# wireless-therm-mk2.net
KiCad netlist of a schematic drawn in EAGLE
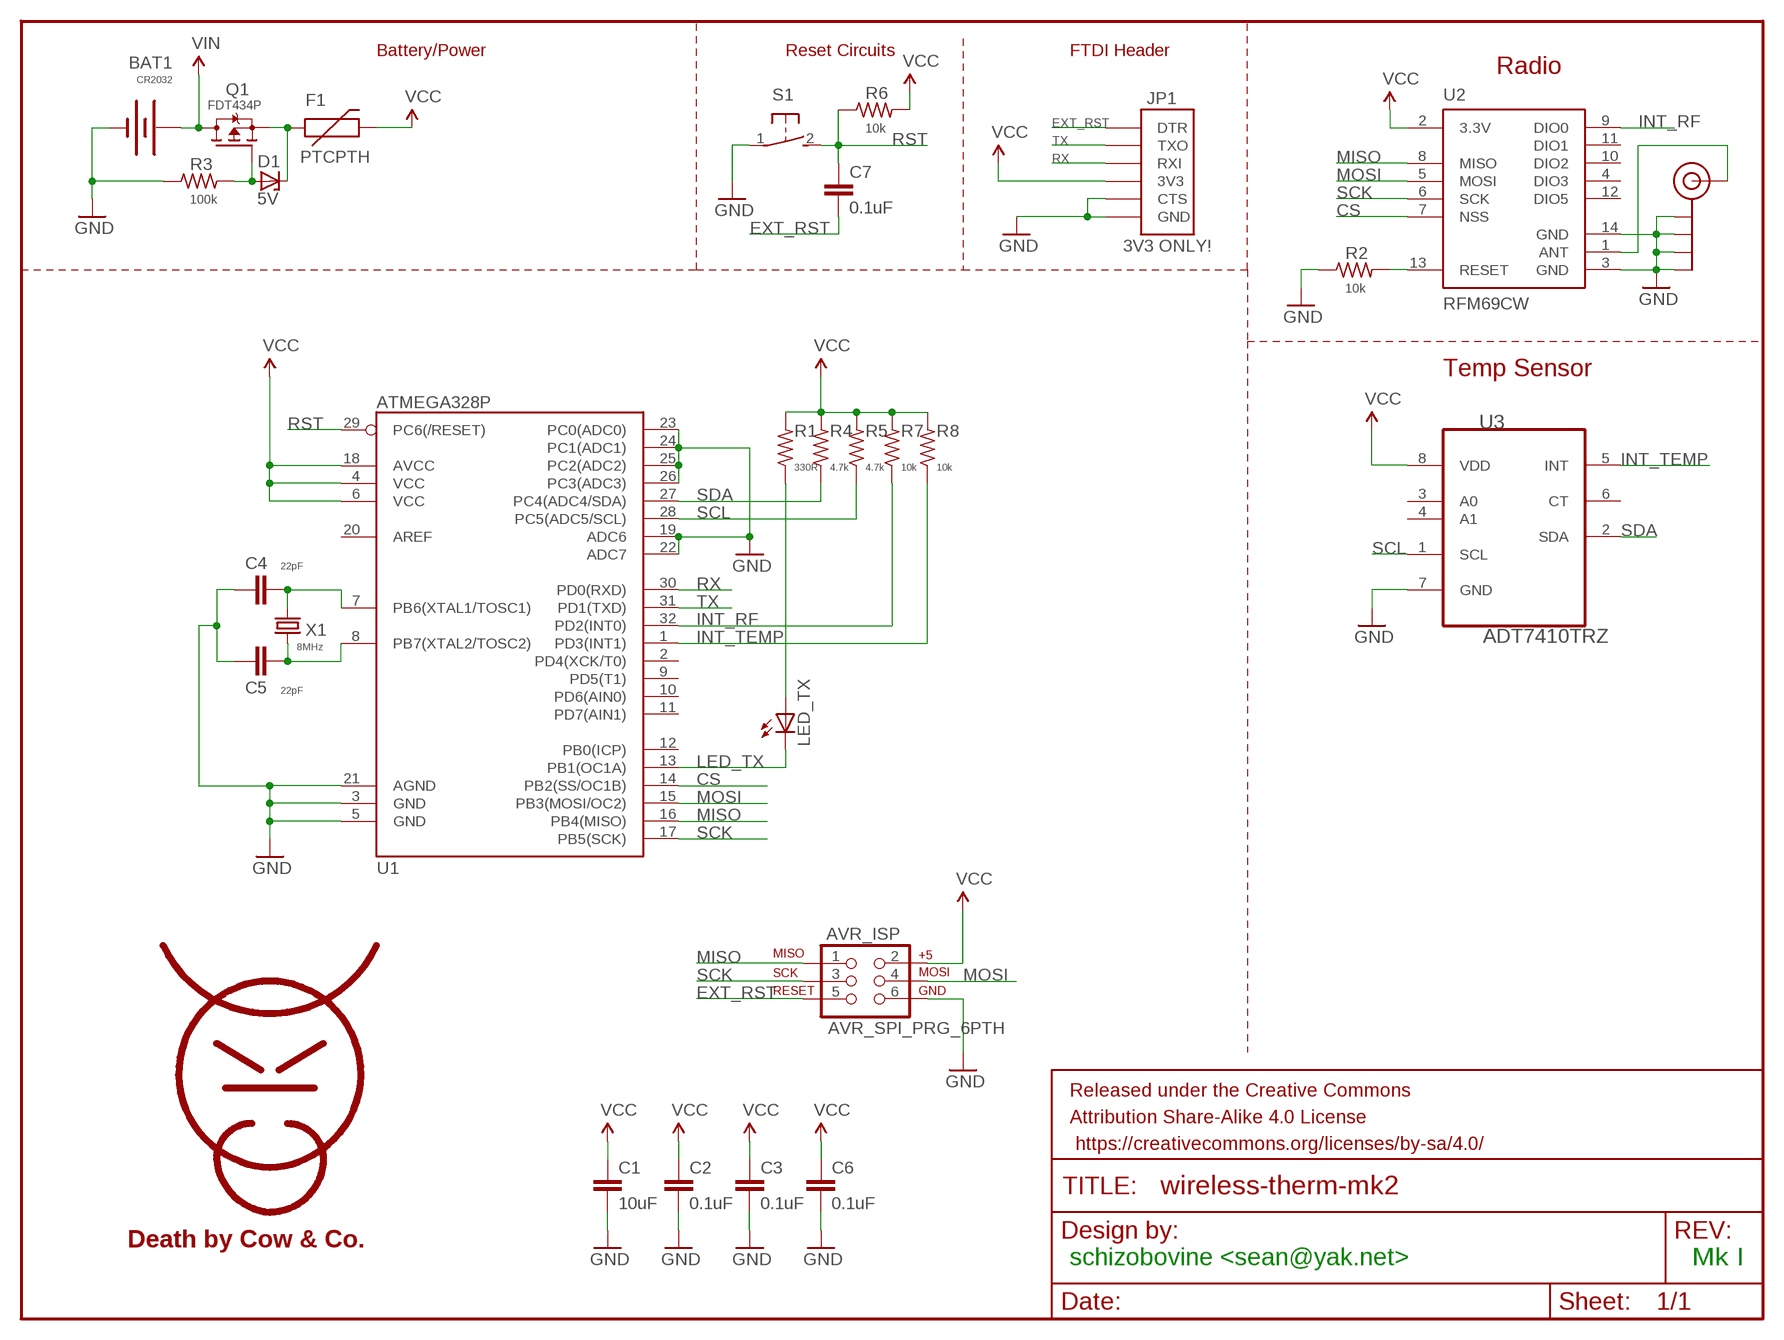
[diagram p0: schematic, sheet 1]

(export (version "E")
  (design (tool "Eeschema 10.0.6"))
  (components
    (comp (ref "AVR_ISP")
      (value "AVR_SPI_PRG_6PTH")
      (footprint "eagle-import:2X3")
      (libsource (lib "eagle-import") (part "AVR_SPI_PRG_6PTH"))
    )
    (comp (ref "BAT1")
      (value "CR2032")
      (footprint "eagle-import:BATTCON_20MM")
      (libsource (lib "eagle-import") (part "BATTERY20SMD"))
    )
    (comp (ref "C1")
      (value "10uF")
      (footprint "eagle-import:C050-025X075")
      (libsource (lib "eagle-import") (part "C-EU050-025X075"))
    )
    (comp (ref "C2")
      (value "0.1uF")
      (footprint "eagle-import:C025-025X050")
      (libsource (lib "eagle-import") (part "C-EU025-025X050"))
    )
    (comp (ref "C3")
      (value "0.1uF")
      (footprint "eagle-import:C025-025X050")
      (libsource (lib "eagle-import") (part "C-EU025-025X050"))
    )
    (comp (ref "C4")
      (value "22pF")
      (footprint "eagle-import:C025-025X050")
      (libsource (lib "eagle-import") (part "C-EU025-025X050"))
    )
    (comp (ref "C5")
      (value "22pF")
      (footprint "eagle-import:C025-025X050")
      (libsource (lib "eagle-import") (part "C-EU025-025X050"))
    )
    (comp (ref "C6")
      (value "0.1uF")
      (footprint "eagle-import:C025-025X050")
      (libsource (lib "eagle-import") (part "C-EU025-025X050"))
    )
    (comp (ref "C7")
      (value "0.1uF")
      (footprint "eagle-import:C025-025X050")
      (libsource (lib "eagle-import") (part "C-EU025-025X050"))
    )
    (comp (ref "D1")
      (value "5V")
      (footprint "eagle-import:DO34Z7")
      (libsource (lib "eagle-import") (part "ZENER-DIODEDO34-7"))
    )
    (comp (ref "F1")
      (value "PTCPTH")
      (footprint "eagle-import:PTC")
      (libsource (lib "eagle-import") (part "PTCPTH"))
    )
    (comp (ref "FRAME1")
      (value "FRAME-LETTER")
      (footprint "eagle-import:CREATIVE_COMMONS")
      (libsource (lib "eagle-import") (part "FRAME-LETTER"))
    )
    (comp (ref "JP1")
      (value "3V3 ONLY!")
      (footprint "eagle-import:FTDI_3V3")
      (libsource (lib "eagle-import") (part "FTDI_3V3"))
    )
    (comp (ref "LED_TX")
      (value "GREEN")
      (footprint "eagle-import:LED3MM")
      (libsource (lib "eagle-import") (part "LED3MM"))
    )
    (comp (ref "Q1")
      (value "FDT434P")
      (footprint "eagle-import:SOT223")
      (libsource (lib "eagle-import") (part "FDT434P"))
    )
    (comp (ref "R1")
      (value "330R")
      (footprint "eagle-import:0204_5")
      (libsource (lib "eagle-import") (part "R-US_0204/5"))
    )
    (comp (ref "R2")
      (value "10k")
      (footprint "eagle-import:0204_5")
      (libsource (lib "eagle-import") (part "R-US_0204/5"))
    )
    (comp (ref "R3")
      (value "100k")
      (footprint "eagle-import:0204_5")
      (libsource (lib "eagle-import") (part "R-US_0204/5"))
    )
    (comp (ref "R4")
      (value "4.7k")
      (footprint "eagle-import:0204_5")
      (libsource (lib "eagle-import") (part "R-US_0204/5"))
    )
    (comp (ref "R5")
      (value "4.7k")
      (footprint "eagle-import:0204_5")
      (libsource (lib "eagle-import") (part "R-US_0204/5"))
    )
    (comp (ref "R6")
      (value "10k")
      (footprint "eagle-import:0204_5")
      (libsource (lib "eagle-import") (part "R-US_0204/5"))
    )
    (comp (ref "R7")
      (value "10k")
      (footprint "eagle-import:0204_5")
      (libsource (lib "eagle-import") (part "R-US_0204/5"))
    )
    (comp (ref "R8")
      (value "10k")
      (footprint "eagle-import:0204_5")
      (libsource (lib "eagle-import") (part "R-US_0204/5"))
    )
    (comp (ref "S1")
      (value "DTS-3")
      (footprint "eagle-import:DTS-3")
      (libsource (lib "eagle-import") (part "DTS-3"))
    )
    (comp (ref "SMA_CON")
      (value "SMA_EDGE")
      (footprint "eagle-import:SMA-EDGE")
      (libsource (lib "eagle-import") (part "SMA_EDGE"))
    )
    (comp (ref "U$4")
      (value "COW")
      (footprint "eagle-import:COW")
      (libsource (lib "eagle-import") (part "COW"))
    )
    (comp (ref "U1")
      (value "ATMEGA328P")
      (footprint "eagle-import:TQFP32-08")
      (libsource (lib "eagle-import") (part "ATMEGA328_SMT"))
    )
    (comp (ref "U2")
      (value "RFM69CW")
      (footprint "eagle-import:RFM69CW-XXXS2")
      (libsource (lib "eagle-import") (part "RFM69CW"))
    )
    (comp (ref "U3")
      (value "ADT7410TRZ")
      (footprint "eagle-import:SOIC127P600X175-8N")
      (libsource (lib "eagle-import") (part "ADT7410TRZ"))
    )
    (comp (ref "X1")
      (value "8MHz")
      (footprint "eagle-import:HC49U70")
      (libsource (lib "eagle-import") (part "CRYSTALHC49U70"))
    )
  )
  (nets
    (net (code "1") (name "/CS") (class "Default")
      (node (ref "U1") (pin "14") (pinfunction "PB2(SS/OC1B)_14") (pintype "bidirectional"))
      (node (ref "U2") (pin "7") (pinfunction "NSS_7") (pintype "input"))
    )
    (net (code "2") (name "/EXT_RST") (class "Default")
      (node (ref "AVR_ISP") (pin "5") (pinfunction "5_5") (pintype "passive"))
      (node (ref "C7") (pin "2") (pinfunction "2_2") (pintype "passive"))
      (node (ref "JP1") (pin "P$1") (pinfunction "DTR_P$1") (pintype "bidirectional"))
    )
    (net (code "3") (name "/INT_RF") (class "Default")
      (node (ref "R7") (pin "1") (pinfunction "1_1") (pintype "passive"))
      (node (ref "U1") (pin "32") (pinfunction "PD2(INT0)_32") (pintype "bidirectional"))
      (node (ref "U2") (pin "9") (pinfunction "DIO0_9") (pintype "bidirectional"))
    )
    (net (code "4") (name "/INT_TEMP") (class "Default")
      (node (ref "R8") (pin "1") (pinfunction "1_1") (pintype "passive"))
      (node (ref "U1") (pin "1") (pinfunction "PD3(INT1)_1") (pintype "bidirectional"))
      (node (ref "U3") (pin "5") (pinfunction "INT_5") (pintype "output"))
    )
    (net (code "5") (name "/LED_TX") (class "Default")
      (node (ref "LED_TX") (pin "K") (pinfunction "C_K") (pintype "passive"))
      (node (ref "U1") (pin "13") (pinfunction "PB1(OC1A)_13") (pintype "bidirectional"))
    )
    (net (code "6") (name "/MISO") (class "Default")
      (node (ref "AVR_ISP") (pin "1") (pinfunction "1_1") (pintype "passive"))
      (node (ref "U1") (pin "16") (pinfunction "PB4(MISO)_16") (pintype "bidirectional"))
      (node (ref "U2") (pin "8") (pinfunction "MISO_8") (pintype "bidirectional"))
    )
    (net (code "7") (name "/MOSI") (class "Default")
      (node (ref "AVR_ISP") (pin "4") (pinfunction "4_4") (pintype "passive"))
      (node (ref "U1") (pin "15") (pinfunction "PB3(MOSI/OC2)_15") (pintype "bidirectional"))
      (node (ref "U2") (pin "5") (pinfunction "MOSI_5") (pintype "input"))
    )
    (net (code "8") (name "/RST") (class "Default")
      (node (ref "C7") (pin "1") (pinfunction "1_1") (pintype "passive"))
      (node (ref "R6") (pin "1") (pinfunction "1_1") (pintype "passive"))
      (node (ref "S1") (pin "2") (pinfunction "2_2") (pintype "passive"))
      (node (ref "U1") (pin "29") (pinfunction "PC6(/RESET)_29") (pintype "bidirectional"))
    )
    (net (code "9") (name "/RX") (class "Default")
      (node (ref "JP1") (pin "P$3") (pinfunction "RXI_P$3") (pintype "bidirectional"))
      (node (ref "U1") (pin "30") (pinfunction "PD0(RXD)_30") (pintype "bidirectional"))
    )
    (net (code "10") (name "/SCK") (class "Default")
      (node (ref "AVR_ISP") (pin "3") (pinfunction "3_3") (pintype "passive"))
      (node (ref "U1") (pin "17") (pinfunction "PB5(SCK)_17") (pintype "bidirectional"))
      (node (ref "U2") (pin "6") (pinfunction "SCK_6") (pintype "input"))
    )
    (net (code "11") (name "/SCL") (class "Default")
      (node (ref "R5") (pin "1") (pinfunction "1_1") (pintype "passive"))
      (node (ref "U1") (pin "28") (pinfunction "PC5(ADC5/SCL)_28") (pintype "bidirectional"))
      (node (ref "U3") (pin "1") (pinfunction "SCL_1") (pintype "input"))
    )
    (net (code "12") (name "/SDA") (class "Default")
      (node (ref "R4") (pin "1") (pinfunction "1_1") (pintype "passive"))
      (node (ref "U1") (pin "27") (pinfunction "PC4(ADC4/SDA)_27") (pintype "bidirectional"))
      (node (ref "U3") (pin "2") (pinfunction "SDA_2") (pintype "bidirectional"))
    )
    (net (code "13") (name "/TX") (class "Default")
      (node (ref "JP1") (pin "P$2") (pinfunction "TXO_P$2") (pintype "bidirectional"))
      (node (ref "U1") (pin "31") (pinfunction "PD1(TXD)_31") (pintype "bidirectional"))
    )
    (net (code "14") (name "GND") (class "Default")
      (node (ref "AVR_ISP") (pin "6") (pinfunction "6_6") (pintype "passive"))
      (node (ref "BAT1") (pin "2") (pinfunction "-_2") (pintype "power_in"))
      (node (ref "C1") (pin "2") (pinfunction "2_2") (pintype "passive"))
      (node (ref "C2") (pin "2") (pinfunction "2_2") (pintype "passive"))
      (node (ref "C3") (pin "2") (pinfunction "2_2") (pintype "passive"))
      (node (ref "C4") (pin "1") (pinfunction "1_1") (pintype "passive"))
      (node (ref "C5") (pin "1") (pinfunction "1_1") (pintype "passive"))
      (node (ref "C6") (pin "2") (pinfunction "2_2") (pintype "passive"))
      (node (ref "JP1") (pin "P$5") (pinfunction "CTS_P$5") (pintype "bidirectional"))
      (node (ref "JP1") (pin "P$6") (pinfunction "GND_P$6") (pintype "bidirectional"))
      (node (ref "R2") (pin "1") (pinfunction "1_1") (pintype "passive"))
      (node (ref "R3") (pin "1") (pinfunction "1_1") (pintype "passive"))
      (node (ref "S1") (pin "1") (pinfunction "1_1") (pintype "passive"))
      (node (ref "SMA_CON") (pin "GND@0") (pinfunction "GND_GND@0") (pintype "bidirectional"))
      (node (ref "SMA_CON") (pin "GND@1") (pinfunction "GND_GND@1") (pintype "bidirectional"))
      (node (ref "SMA_CON") (pin "GND@2") (pinfunction "GND_GND@2") (pintype "bidirectional"))
      (node (ref "SMA_CON") (pin "GND@3") (pinfunction "GND_GND@3") (pintype "bidirectional"))
      (node (ref "U1") (pin "19") (pinfunction "ADC6_19") (pintype "bidirectional"))
      (node (ref "U1") (pin "21") (pinfunction "AGND_21") (pintype "bidirectional"))
      (node (ref "U1") (pin "22") (pinfunction "ADC7_22") (pintype "bidirectional"))
      (node (ref "U1") (pin "23") (pinfunction "PC0(ADC0)_23") (pintype "bidirectional"))
      (node (ref "U1") (pin "24") (pinfunction "PC1(ADC1)_24") (pintype "bidirectional"))
      (node (ref "U1") (pin "25") (pinfunction "PC2(ADC2)_25") (pintype "bidirectional"))
      (node (ref "U1") (pin "26") (pinfunction "PC3(ADC3)_26") (pintype "bidirectional"))
      (node (ref "U1") (pin "3") (pinfunction "GND_3") (pintype "bidirectional"))
      (node (ref "U1") (pin "5") (pinfunction "GND_5") (pintype "bidirectional"))
      (node (ref "U2") (pin "14") (pinfunction "GND_14") (pintype "power_in"))
      (node (ref "U2") (pin "3") (pinfunction "GND_3") (pintype "power_in"))
      (node (ref "U3") (pin "7") (pinfunction "GND_7") (pintype "passive"))
    )
    (net (code "15") (name "Net-(F1-1)") (class "Default")
      (node (ref "D1") (pin "C") (pinfunction "C_C") (pintype "passive"))
      (node (ref "F1") (pin "P$1") (pinfunction "1_P$1") (pintype "bidirectional"))
      (node (ref "Q1") (pin "3") (pinfunction "S_3") (pintype "passive"))
    )
    (net (code "16") (name "Net-(LED_TX-PadA)") (class "Default")
      (node (ref "LED_TX") (pin "A") (pinfunction "A_A") (pintype "passive"))
      (node (ref "R1") (pin "1") (pinfunction "1_1") (pintype "passive"))
    )
    (net (code "17") (name "Net-(Q1-G)") (class "Default")
      (node (ref "D1") (pin "A") (pinfunction "A_A") (pintype "passive"))
      (node (ref "Q1") (pin "1") (pinfunction "G_1") (pintype "passive"))
      (node (ref "R3") (pin "2") (pinfunction "2_2") (pintype "passive"))
    )
    (net (code "18") (name "Net-(SMA_CON-SIGNAL)") (class "Default")
      (node (ref "SMA_CON") (pin "SIG") (pinfunction "SIGNAL_SIG") (pintype "bidirectional"))
      (node (ref "U2") (pin "1") (pinfunction "ANT_1") (pintype "passive"))
    )
    (net (code "19") (name "Net-(U1-PB6(XTAL1{slash}TOSC1))") (class "Default")
      (node (ref "C4") (pin "2") (pinfunction "2_2") (pintype "passive"))
      (node (ref "U1") (pin "7") (pinfunction "PB6(XTAL1/TOSC1)_7") (pintype "bidirectional"))
      (node (ref "X1") (pin "2") (pinfunction "2_2") (pintype "passive"))
    )
    (net (code "20") (name "Net-(U1-PB7(XTAL2{slash}TOSC2))") (class "Default")
      (node (ref "C5") (pin "2") (pinfunction "2_2") (pintype "passive"))
      (node (ref "U1") (pin "8") (pinfunction "PB7(XTAL2/TOSC2)_8") (pintype "bidirectional"))
      (node (ref "X1") (pin "1") (pinfunction "1_1") (pintype "passive"))
    )
    (net (code "21") (name "Net-(U2-RESET)") (class "Default")
      (node (ref "R2") (pin "2") (pinfunction "2_2") (pintype "passive"))
      (node (ref "U2") (pin "13") (pinfunction "RESET_13") (pintype "input"))
    )
    (net (code "22") (name "VCC") (class "Default")
      (node (ref "AVR_ISP") (pin "2") (pinfunction "2_2") (pintype "passive"))
      (node (ref "C1") (pin "1") (pinfunction "1_1") (pintype "passive"))
      (node (ref "C2") (pin "1") (pinfunction "1_1") (pintype "passive"))
      (node (ref "C3") (pin "1") (pinfunction "1_1") (pintype "passive"))
      (node (ref "C6") (pin "1") (pinfunction "1_1") (pintype "passive"))
      (node (ref "F1") (pin "P$2") (pinfunction "2_P$2") (pintype "bidirectional"))
      (node (ref "JP1") (pin "P$4") (pinfunction "3V3_P$4") (pintype "bidirectional"))
      (node (ref "R1") (pin "2") (pinfunction "2_2") (pintype "passive"))
      (node (ref "R4") (pin "2") (pinfunction "2_2") (pintype "passive"))
      (node (ref "R5") (pin "2") (pinfunction "2_2") (pintype "passive"))
      (node (ref "R6") (pin "2") (pinfunction "2_2") (pintype "passive"))
      (node (ref "R7") (pin "2") (pinfunction "2_2") (pintype "passive"))
      (node (ref "R8") (pin "2") (pinfunction "2_2") (pintype "passive"))
      (node (ref "U1") (pin "18") (pinfunction "AVCC_18") (pintype "bidirectional"))
      (node (ref "U1") (pin "4") (pinfunction "VCC_4") (pintype "bidirectional"))
      (node (ref "U1") (pin "6") (pinfunction "VCC_6") (pintype "bidirectional"))
      (node (ref "U2") (pin "2") (pinfunction "3.3V_2") (pintype "power_in"))
      (node (ref "U3") (pin "8") (pinfunction "VDD_8") (pintype "power_in"))
    )
    (net (code "23") (name "VIN") (class "Default")
      (node (ref "BAT1") (pin "1") (pinfunction "+_1") (pintype "power_in"))
      (node (ref "Q1") (pin "2") (pinfunction "D_2") (pintype "passive"))
      (node (ref "Q1") (pin "4") (pinfunction "D_4") (pintype "passive"))
    )
    (net (code "24") (name "unconnected-(U1-AREF-Pad20)") (class "Default")
      (node (ref "U1") (pin "20") (pinfunction "AREF_20") (pintype "bidirectional"))
    )
    (net (code "25") (name "unconnected-(U1-PB0(ICP)-Pad12)") (class "Default")
      (node (ref "U1") (pin "12") (pinfunction "PB0(ICP)_12") (pintype "bidirectional"))
    )
    (net (code "26") (name "unconnected-(U1-PD4(XCK{slash}T0)-Pad2)") (class "Default")
      (node (ref "U1") (pin "2") (pinfunction "PD4(XCK/T0)_2") (pintype "bidirectional"))
    )
    (net (code "27") (name "unconnected-(U1-PD5(T1)-Pad9)") (class "Default")
      (node (ref "U1") (pin "9") (pinfunction "PD5(T1)_9") (pintype "bidirectional"))
    )
    (net (code "28") (name "unconnected-(U1-PD6(AIN0)-Pad10)") (class "Default")
      (node (ref "U1") (pin "10") (pinfunction "PD6(AIN0)_10") (pintype "bidirectional"))
    )
    (net (code "29") (name "unconnected-(U1-PD7(AIN1)-Pad11)") (class "Default")
      (node (ref "U1") (pin "11") (pinfunction "PD7(AIN1)_11") (pintype "bidirectional"))
    )
    (net (code "30") (name "unconnected-(U2-DIO1-Pad11)") (class "Default")
      (node (ref "U2") (pin "11") (pinfunction "DIO1_11") (pintype "bidirectional"))
    )
    (net (code "31") (name "unconnected-(U2-DIO2-Pad10)") (class "Default")
      (node (ref "U2") (pin "10") (pinfunction "DIO2_10") (pintype "bidirectional"))
    )
    (net (code "32") (name "unconnected-(U2-DIO3-Pad4)") (class "Default")
      (node (ref "U2") (pin "4") (pinfunction "DIO3_4") (pintype "bidirectional"))
    )
    (net (code "33") (name "unconnected-(U2-DIO5-Pad12)") (class "Default")
      (node (ref "U2") (pin "12") (pinfunction "DIO5_12") (pintype "bidirectional"))
    )
    (net (code "34") (name "unconnected-(U3-A0-Pad3)") (class "Default")
      (node (ref "U3") (pin "3") (pinfunction "A0_3") (pintype "input"))
    )
    (net (code "35") (name "unconnected-(U3-A1-Pad4)") (class "Default")
      (node (ref "U3") (pin "4") (pinfunction "A1_4") (pintype "input"))
    )
    (net (code "36") (name "unconnected-(U3-CT-Pad6)") (class "Default")
      (node (ref "U3") (pin "6") (pinfunction "CT_6") (pintype "output"))
    )
  )
)
